# board_v2.net
KiCad netlist of a schematic drawn in EAGLE
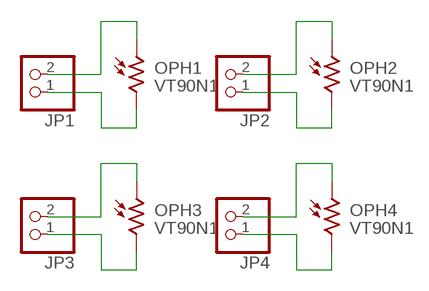
[diagram p0: schematic, sheet 1]

(export (version "E")
  (design (tool "Eeschema 10.0.6"))
  (components
    (comp (ref "JP1")
      (value "PINHD-1X2")
      (footprint "eagle-import:1X02")
      (libsource (lib "eagle-import") (part "PINHD-1X2"))
    )
    (comp (ref "JP2")
      (value "PINHD-1X2")
      (footprint "eagle-import:1X02")
      (libsource (lib "eagle-import") (part "PINHD-1X2"))
    )
    (comp (ref "JP3")
      (value "PINHD-1X2")
      (footprint "eagle-import:1X02")
      (libsource (lib "eagle-import") (part "PINHD-1X2"))
    )
    (comp (ref "JP4")
      (value "PINHD-1X2")
      (footprint "eagle-import:1X02")
      (libsource (lib "eagle-import") (part "PINHD-1X2"))
    )
    (comp (ref "OPH1")
      (value "VT90N1")
      (footprint "eagle-import:VT900")
      (libsource (lib "eagle-import") (part "VT90N1"))
    )
    (comp (ref "OPH2")
      (value "VT90N1")
      (footprint "eagle-import:VT900")
      (libsource (lib "eagle-import") (part "VT90N1"))
    )
    (comp (ref "OPH3")
      (value "VT90N1")
      (footprint "eagle-import:VT900")
      (libsource (lib "eagle-import") (part "VT90N1"))
    )
    (comp (ref "OPH4")
      (value "VT90N1")
      (footprint "eagle-import:VT900")
      (libsource (lib "eagle-import") (part "VT90N1"))
    )
  )
  (nets
    (net (code "1") (name "Net-(JP1-Pad1)") (class "Default")
      (node (ref "JP1") (pin "1") (pinfunction "1_1") (pintype "passive"))
      (node (ref "OPH1") (pin "2") (pinfunction "2_2") (pintype "passive"))
    )
    (net (code "2") (name "Net-(JP1-Pad2)") (class "Default")
      (node (ref "JP1") (pin "2") (pinfunction "2_2") (pintype "passive"))
      (node (ref "OPH1") (pin "1") (pinfunction "1_1") (pintype "passive"))
    )
    (net (code "3") (name "Net-(JP2-Pad1)") (class "Default")
      (node (ref "JP2") (pin "1") (pinfunction "1_1") (pintype "passive"))
      (node (ref "OPH2") (pin "2") (pinfunction "2_2") (pintype "passive"))
    )
    (net (code "4") (name "Net-(JP2-Pad2)") (class "Default")
      (node (ref "JP2") (pin "2") (pinfunction "2_2") (pintype "passive"))
      (node (ref "OPH2") (pin "1") (pinfunction "1_1") (pintype "passive"))
    )
    (net (code "5") (name "Net-(JP3-Pad1)") (class "Default")
      (node (ref "JP3") (pin "1") (pinfunction "1_1") (pintype "passive"))
      (node (ref "OPH3") (pin "2") (pinfunction "2_2") (pintype "passive"))
    )
    (net (code "6") (name "Net-(JP3-Pad2)") (class "Default")
      (node (ref "JP3") (pin "2") (pinfunction "2_2") (pintype "passive"))
      (node (ref "OPH3") (pin "1") (pinfunction "1_1") (pintype "passive"))
    )
    (net (code "7") (name "Net-(JP4-Pad1)") (class "Default")
      (node (ref "JP4") (pin "1") (pinfunction "1_1") (pintype "passive"))
      (node (ref "OPH4") (pin "2") (pinfunction "2_2") (pintype "passive"))
    )
    (net (code "8") (name "Net-(JP4-Pad2)") (class "Default")
      (node (ref "JP4") (pin "2") (pinfunction "2_2") (pintype "passive"))
      (node (ref "OPH4") (pin "1") (pinfunction "1_1") (pintype "passive"))
    )
  )
)
